# EXT_LASER.net
KiCad netlist of a schematic drawn in Altium Designer
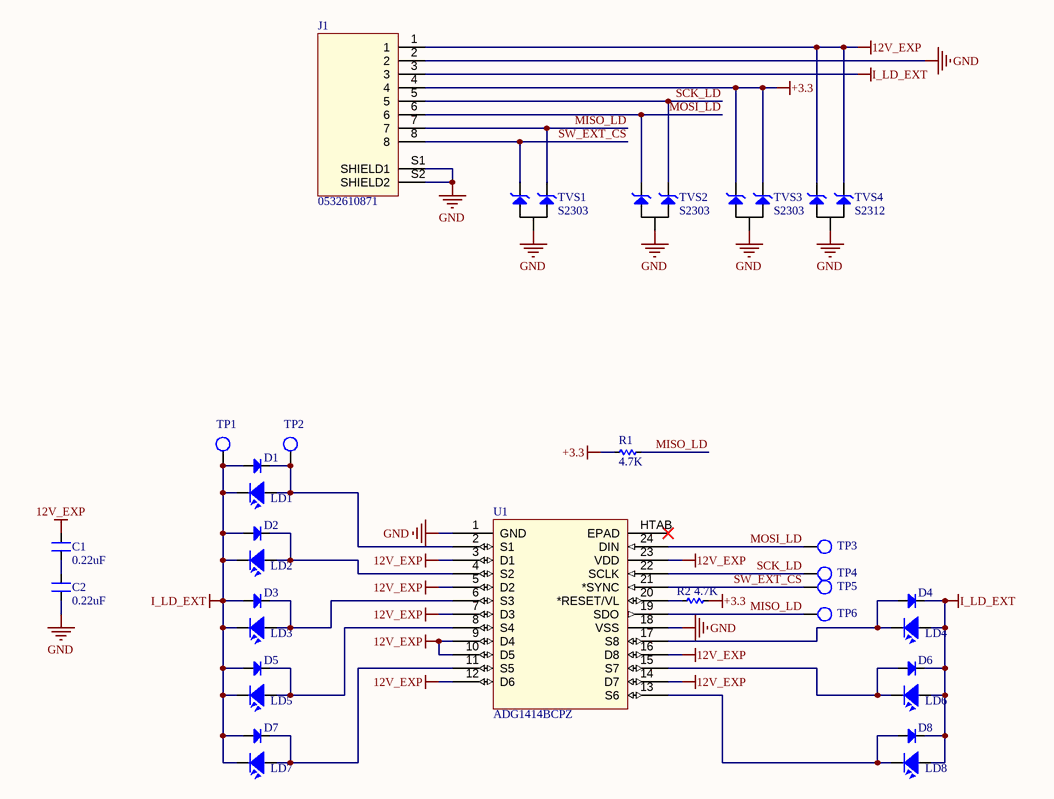
[diagram p0: EXT_LASER.SchDoc]

(export (version "E")
  (design (tool "Eeschema 10.0.6"))
  (components
    (comp (ref "C1") (value "0.22uF") (footprint "CN-SMD-0603") (libsource (lib "Library") (part "CN")))
    (comp (ref "C2") (value "0.22uF") (footprint "CN-SMD-0603") (libsource (lib "Library") (part "CN")))
    (comp (ref "D1")
      (value "Diode SMD")
      (footprint "DIO-SMD-123")
      (description "Default Diode")
      (fields (field (name "PUBLISHER") "Altium Limited"))
      (libsource (lib "Library") (part "Diode SMD"))
    )
    (comp (ref "D2")
      (value "Diode SMD")
      (footprint "DIO-SMD-123")
      (description "Default Diode")
      (fields (field (name "PUBLISHER") "Altium Limited"))
      (libsource (lib "Library") (part "Diode SMD"))
    )
    (comp (ref "D3")
      (value "Diode SMD")
      (footprint "DIO-SMD-123")
      (description "Default Diode")
      (fields (field (name "PUBLISHER") "Altium Limited"))
      (libsource (lib "Library") (part "Diode SMD"))
    )
    (comp (ref "D4")
      (value "Diode SMD")
      (footprint "DIO-SMD-123")
      (description "Default Diode")
      (fields (field (name "PUBLISHER") "Altium Limited"))
      (libsource (lib "Library") (part "Diode SMD"))
    )
    (comp (ref "D5")
      (value "Diode SMD")
      (footprint "DIO-SMD-123")
      (description "Default Diode")
      (fields (field (name "PUBLISHER") "Altium Limited"))
      (libsource (lib "Library") (part "Diode SMD"))
    )
    (comp (ref "D6")
      (value "Diode SMD")
      (footprint "DIO-SMD-123")
      (description "Default Diode")
      (fields (field (name "PUBLISHER") "Altium Limited"))
      (libsource (lib "Library") (part "Diode SMD"))
    )
    (comp (ref "D7")
      (value "Diode SMD")
      (footprint "DIO-SMD-123")
      (description "Default Diode")
      (fields (field (name "PUBLISHER") "Altium Limited"))
      (libsource (lib "Library") (part "Diode SMD"))
    )
    (comp (ref "D8")
      (value "Diode SMD")
      (footprint "DIO-SMD-123")
      (description "Default Diode")
      (fields (field (name "PUBLISHER") "Altium Limited"))
      (libsource (lib "Library") (part "Diode SMD"))
    )
    (comp (ref "J1")
      (value "0532610871")
      (footprint "0532610871")
      (description "Header 8 + Shield")
      (libsource (lib "Library") (part "Header8 - Shield"))
    )
    (comp (ref "LD1")
      (value "LED")
      (footprint "LED-3MM-YELLOW")
      (description "LED Single colour Green and Red")
      (libsource (lib "Library") (part "LED"))
    )
    (comp (ref "LD2")
      (value "LED")
      (footprint "LED-3MM-YELLOW")
      (description "LED Single colour Green and Red")
      (libsource (lib "Library") (part "LED"))
    )
    (comp (ref "LD3")
      (value "LED")
      (footprint "LED-3MM-YELLOW")
      (description "LED Single colour Green and Red")
      (libsource (lib "Library") (part "LED"))
    )
    (comp (ref "LD4")
      (value "LED")
      (footprint "LED-3MM-YELLOW")
      (description "LED Single colour Green and Red")
      (libsource (lib "Library") (part "LED"))
    )
    (comp (ref "LD5")
      (value "LED")
      (footprint "LED-3MM-YELLOW")
      (description "LED Single colour Green and Red")
      (libsource (lib "Library") (part "LED"))
    )
    (comp (ref "LD6")
      (value "LED")
      (footprint "LED-3MM-YELLOW")
      (description "LED Single colour Green and Red")
      (libsource (lib "Library") (part "LED"))
    )
    (comp (ref "LD7")
      (value "LED")
      (footprint "LED-3MM-YELLOW")
      (description "LED Single colour Green and Red")
      (libsource (lib "Library") (part "LED"))
    )
    (comp (ref "LD8")
      (value "LED")
      (footprint "LED-3MM-YELLOW")
      (description "LED Single colour Green and Red")
      (libsource (lib "Library") (part "LED"))
    )
    (comp (ref "R1")
      (value "4.7K")
      (footprint "RES-SMD-0603")
      (description "Resistor")
      (fields
        (field (name "MANUFACTURER") "Generic Components")
        (field (name "PUBLISHER") "Altium Hobart Technology Centre")
      )
      (libsource (lib "Library") (part "Res-SMD"))
    )
    (comp (ref "R2")
      (value "4.7K")
      (footprint "RES-SMD-0603")
      (description "Resistor")
      (fields
        (field (name "MANUFACTURER") "Generic Components")
        (field (name "PUBLISHER") "Altium Hobart Technology Centre")
      )
      (libsource (lib "Library") (part "Res-SMD"))
    )
    (comp (ref "TP1")
      (value "Test-Point")
      (footprint "TESTPOINT")
      (libsource (lib "Library") (part "Test-Point"))
    )
    (comp (ref "TP2")
      (value "Test-Point")
      (footprint "TESTPOINT")
      (libsource (lib "Library") (part "Test-Point"))
    )
    (comp (ref "TP3")
      (value "Test-Point")
      (footprint "TESTPOINT")
      (libsource (lib "Library") (part "Test-Point"))
    )
    (comp (ref "TP4")
      (value "Test-Point")
      (footprint "TESTPOINT")
      (libsource (lib "Library") (part "Test-Point"))
    )
    (comp (ref "TP5")
      (value "Test-Point")
      (footprint "TESTPOINT")
      (libsource (lib "Library") (part "Test-Point"))
    )
    (comp (ref "TP6")
      (value "Test-Point")
      (footprint "TESTPOINT")
      (libsource (lib "Library") (part "Test-Point"))
    )
    (comp (ref "TVS1")
      (value "S2303")
      (footprint "SOT23-123")
      (description "TVS DIODE 3.3VWM 8VC SOT23, P/N:  \r\nS2303")
      (libsource (lib "Library") (part "S2303"))
    )
    (comp (ref "TVS2")
      (value "S2303")
      (footprint "SOT23-123")
      (description "TVS DIODE 3.3VWM 8VC SOT23, P/N:  \r\nS2303")
      (libsource (lib "Library") (part "S2303"))
    )
    (comp (ref "TVS3")
      (value "S2303")
      (footprint "SOT23-123")
      (description "TVS DIODE 3.3VWM 8VC SOT23, P/N:  \r\nS2303")
      (libsource (lib "Library") (part "S2303"))
    )
    (comp (ref "TVS4")
      (value "S2312")
      (footprint "SOT23-123")
      (description "TVS DIODE 12VWM 19VC SOT233")
      (libsource (lib "Library") (part "S2315"))
    )
    (comp (ref "U1")
      (value "ADG1414BCPZ")
      (footprint "ADG1414BCPZ")
      (description "IC SW SPST-NOX8 11.5OHM 24LFCSP")
      (libsource (lib "Library") (part "ADG1414BCPZ"))
    )
  )
  (nets
    (net (code "1") (name "+3.3") (class "Default")
      (node (ref "J1") (pin "4") (pinfunction "4_4") (pintype "passive"))
      (node (ref "R1") (pin "1") (pinfunction "1_1") (pintype "passive"))
      (node (ref "R2") (pin "1") (pinfunction "1_1") (pintype "passive"))
      (node (ref "TVS3") (pin "1") (pintype "passive"))
      (node (ref "TVS3") (pin "3") (pintype "passive"))
    )
    (net (code "2") (name "/MISO_LD") (class "Default")
      (node (ref "J1") (pin "7") (pinfunction "7_7") (pintype "passive"))
      (node (ref "R1") (pin "2") (pinfunction "2_2") (pintype "passive"))
      (node (ref "TP6") (pin "1") (pinfunction "1_1") (pintype "passive"))
      (node (ref "TVS1") (pin "1") (pintype "passive"))
      (node (ref "U1") (pin "19") (pinfunction "SDO_19") (pintype "output"))
    )
    (net (code "3") (name "/MOSI_LD") (class "Default")
      (node (ref "J1") (pin "6") (pinfunction "6_6") (pintype "passive"))
      (node (ref "TP3") (pin "1") (pinfunction "1_1") (pintype "passive"))
      (node (ref "TVS2") (pin "3") (pintype "passive"))
      (node (ref "U1") (pin "24") (pinfunction "DIN_24") (pintype "input"))
    )
    (net (code "4") (name "/SCK_LD") (class "Default")
      (node (ref "J1") (pin "5") (pinfunction "5_5") (pintype "passive"))
      (node (ref "TP4") (pin "1") (pinfunction "1_1") (pintype "passive"))
      (node (ref "TVS2") (pin "1") (pintype "passive"))
      (node (ref "U1") (pin "22") (pinfunction "SCLK_22") (pintype "input"))
    )
    (net (code "5") (name "/SW_EXT_CS") (class "Default")
      (node (ref "J1") (pin "8") (pinfunction "8_8") (pintype "passive"))
      (node (ref "TP5") (pin "1") (pinfunction "1_1") (pintype "passive"))
      (node (ref "TVS1") (pin "3") (pintype "passive"))
      (node (ref "U1") (pin "21") (pinfunction "*SYNC_21") (pintype "input"))
    )
    (net (code "6") (name "12V_EXP") (class "Default")
      (node (ref "C1") (pin "2") (pinfunction "2_2") (pintype "passive"))
      (node (ref "J1") (pin "1") (pinfunction "1_1") (pintype "passive"))
      (node (ref "TVS4") (pin "1") (pintype "passive"))
      (node (ref "TVS4") (pin "3") (pintype "passive"))
      (node (ref "U1") (pin "10") (pinfunction "D5_10") (pintype "bidirectional"))
      (node (ref "U1") (pin "12") (pinfunction "D6_12") (pintype "bidirectional"))
      (node (ref "U1") (pin "14") (pinfunction "D7_14") (pintype "bidirectional"))
      (node (ref "U1") (pin "16") (pinfunction "D8_16") (pintype "bidirectional"))
      (node (ref "U1") (pin "23") (pinfunction "VDD_23") (pintype "power_in"))
      (node (ref "U1") (pin "3") (pinfunction "D1_3") (pintype "bidirectional"))
      (node (ref "U1") (pin "5") (pinfunction "D2_5") (pintype "bidirectional"))
      (node (ref "U1") (pin "7") (pinfunction "D3_7") (pintype "bidirectional"))
      (node (ref "U1") (pin "9") (pinfunction "D4_9") (pintype "bidirectional"))
    )
    (net (code "7") (name "GND") (class "Default")
      (node (ref "C2") (pin "1") (pinfunction "1_1") (pintype "passive"))
      (node (ref "J1") (pin "2") (pinfunction "2_2") (pintype "passive"))
      (node (ref "J1") (pin "S1") (pinfunction "SHIELD1_S1") (pintype "passive"))
      (node (ref "J1") (pin "S2") (pinfunction "SHIELD2_S2") (pintype "passive"))
      (node (ref "TVS1") (pin "2") (pintype "passive"))
      (node (ref "TVS2") (pin "2") (pintype "passive"))
      (node (ref "TVS3") (pin "2") (pintype "passive"))
      (node (ref "TVS4") (pin "2") (pintype "passive"))
      (node (ref "U1") (pin "1") (pinfunction "GND_1") (pintype "power_in"))
      (node (ref "U1") (pin "18") (pinfunction "VSS_18") (pintype "power_in"))
    )
    (net (code "8") (name "I_LD_EXT") (class "Default")
      (node (ref "D1") (pin "1") (pinfunction "A_1") (pintype "passive"))
      (node (ref "D2") (pin "1") (pinfunction "A_1") (pintype "passive"))
      (node (ref "D3") (pin "1") (pinfunction "A_1") (pintype "passive"))
      (node (ref "D4") (pin "2") (pinfunction "K_2") (pintype "passive"))
      (node (ref "D5") (pin "1") (pinfunction "A_1") (pintype "passive"))
      (node (ref "D6") (pin "2") (pinfunction "K_2") (pintype "passive"))
      (node (ref "D7") (pin "1") (pinfunction "A_1") (pintype "passive"))
      (node (ref "D8") (pin "2") (pinfunction "K_2") (pintype "passive"))
      (node (ref "J1") (pin "3") (pinfunction "3_3") (pintype "passive"))
      (node (ref "LD1") (pin "2") (pinfunction "2_2") (pintype "passive"))
      (node (ref "LD2") (pin "2") (pinfunction "2_2") (pintype "passive"))
      (node (ref "LD3") (pin "2") (pinfunction "2_2") (pintype "passive"))
      (node (ref "LD4") (pin "1") (pinfunction "1_1") (pintype "passive"))
      (node (ref "LD5") (pin "2") (pinfunction "2_2") (pintype "passive"))
      (node (ref "LD6") (pin "1") (pinfunction "1_1") (pintype "passive"))
      (node (ref "LD7") (pin "2") (pinfunction "2_2") (pintype "passive"))
      (node (ref "LD8") (pin "1") (pinfunction "1_1") (pintype "passive"))
      (node (ref "TP1") (pin "1") (pinfunction "1_1") (pintype "passive"))
    )
    (net (code "9") (name "Net-(C1-Pad1)") (class "Default")
      (node (ref "C1") (pin "1") (pinfunction "1_1") (pintype "passive"))
      (node (ref "C2") (pin "2") (pinfunction "2_2") (pintype "passive"))
    )
    (net (code "10") (name "Net-(D1-K)") (class "Default")
      (node (ref "D1") (pin "2") (pinfunction "K_2") (pintype "passive"))
      (node (ref "LD1") (pin "1") (pinfunction "1_1") (pintype "passive"))
      (node (ref "TP2") (pin "1") (pinfunction "1_1") (pintype "passive"))
      (node (ref "U1") (pin "2") (pinfunction "S1_2") (pintype "bidirectional"))
    )
    (net (code "11") (name "Net-(D2-K)") (class "Default")
      (node (ref "D2") (pin "2") (pinfunction "K_2") (pintype "passive"))
      (node (ref "LD2") (pin "1") (pinfunction "1_1") (pintype "passive"))
      (node (ref "U1") (pin "4") (pinfunction "S2_4") (pintype "bidirectional"))
    )
    (net (code "12") (name "Net-(D3-K)") (class "Default")
      (node (ref "D3") (pin "2") (pinfunction "K_2") (pintype "passive"))
      (node (ref "LD3") (pin "1") (pinfunction "1_1") (pintype "passive"))
      (node (ref "U1") (pin "6") (pinfunction "S3_6") (pintype "bidirectional"))
    )
    (net (code "13") (name "Net-(D4-A)") (class "Default")
      (node (ref "D4") (pin "1") (pinfunction "A_1") (pintype "passive"))
      (node (ref "LD4") (pin "2") (pinfunction "2_2") (pintype "passive"))
      (node (ref "U1") (pin "17") (pinfunction "S8_17") (pintype "bidirectional"))
    )
    (net (code "14") (name "Net-(D5-K)") (class "Default")
      (node (ref "D5") (pin "2") (pinfunction "K_2") (pintype "passive"))
      (node (ref "LD5") (pin "1") (pinfunction "1_1") (pintype "passive"))
      (node (ref "U1") (pin "8") (pinfunction "S4_8") (pintype "bidirectional"))
    )
    (net (code "15") (name "Net-(D6-A)") (class "Default")
      (node (ref "D6") (pin "1") (pinfunction "A_1") (pintype "passive"))
      (node (ref "LD6") (pin "2") (pinfunction "2_2") (pintype "passive"))
      (node (ref "U1") (pin "15") (pinfunction "S7_15") (pintype "bidirectional"))
    )
    (net (code "16") (name "Net-(D7-K)") (class "Default")
      (node (ref "D7") (pin "2") (pinfunction "K_2") (pintype "passive"))
      (node (ref "LD7") (pin "1") (pinfunction "1_1") (pintype "passive"))
      (node (ref "U1") (pin "11") (pinfunction "S5_11") (pintype "bidirectional"))
    )
    (net (code "17") (name "Net-(D8-A)") (class "Default")
      (node (ref "D8") (pin "1") (pinfunction "A_1") (pintype "passive"))
      (node (ref "LD8") (pin "2") (pinfunction "2_2") (pintype "passive"))
      (node (ref "U1") (pin "13") (pinfunction "S6_13") (pintype "bidirectional"))
    )
    (net (code "18") (name "Net-(U1-*RESET{slash}VL)") (class "Default")
      (node (ref "R2") (pin "2") (pinfunction "2_2") (pintype "passive"))
      (node (ref "U1") (pin "20") (pinfunction "*RESET/VL_20") (pintype "bidirectional"))
    )
    (net (code "19") (name "unconnected-(U1-EPAD-PadHTAB)") (class "Default")
      (node (ref "U1") (pin "HTAB") (pinfunction "EPAD_HTAB") (pintype "passive+no_connect"))
    )
  )
)
